# photodiode-opamp-tester-mk-2_0.net
KiCad netlist of a schematic drawn in EAGLE
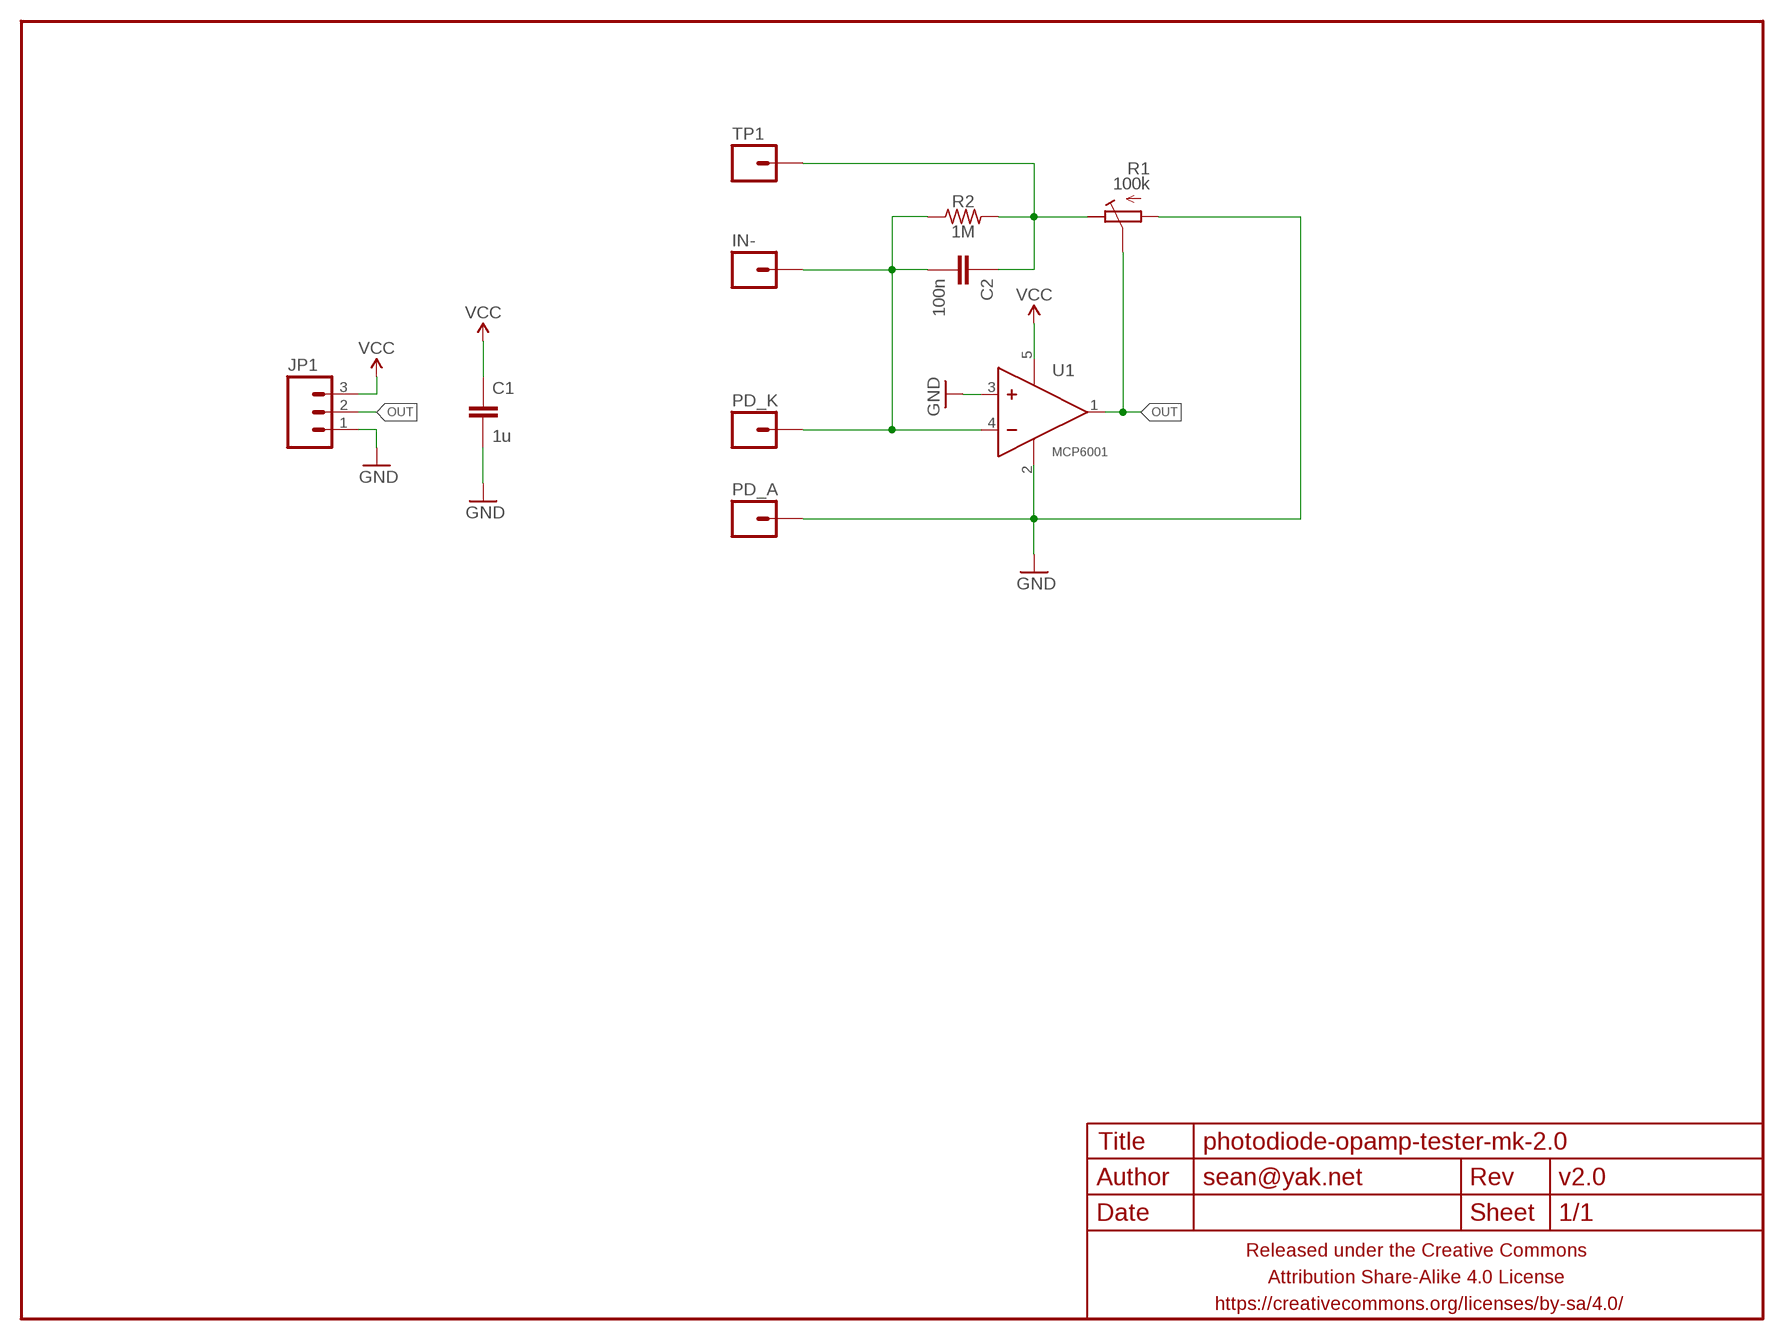
[diagram p0: schematic, sheet 1]

(export (version "E")
  (design (tool "Eeschema 10.0.6"))
  (components
    (comp (ref "C1")
      (value "1u")
      (footprint "eagle-import:C0603")
      (libsource (lib "eagle-import") (part "CAPACITOR-CERAMICC0603"))
    )
    (comp (ref "C2")
      (value "100n")
      (footprint "eagle-import:C0603")
      (libsource (lib "eagle-import") (part "CAPACITOR-CERAMICC0603"))
    )
    (comp (ref "FRAME1")
      (value "FRAME-LETTERNO_PACKAGE")
      (footprint "eagle-import:DUMMY")
      (fields (field (name "DESIGNER") "sean@yak.net") (field (name "VERSION") "v2.0"))
      (libsource (lib "eagle-import") (part "FRAME-LETTERNO_PACKAGE"))
    )
    (comp (ref "IN-")
      (value "M01OFFSET")
      (footprint "eagle-import:1X01_OFFSET")
      (libsource (lib "eagle-import") (part "M01OFFSET"))
    )
    (comp (ref "JP1")
      (value "M03PTH-CENTERED")
      (footprint "eagle-import:1X03-CENTERED")
      (libsource (lib "eagle-import") (part "M03PTH-CENTERED"))
    )
    (comp (ref "PD_A")
      (value "M01PTH-1.2MM-OCT")
      (footprint "eagle-import:1X01-1.2MM-OCT")
      (libsource (lib "eagle-import") (part "M01PTH-1.2MM-OCT"))
    )
    (comp (ref "PD_K")
      (value "M01PTH-1.2MM-OCT")
      (footprint "eagle-import:1X01-1.2MM-OCT")
      (libsource (lib "eagle-import") (part "M01PTH-1.2MM-OCT"))
    )
    (comp (ref "R1")
      (value "100k")
      (footprint "eagle-import:EVM3Y")
      (libsource (lib "eagle-import") (part "POTENTIOMETEREVM3Y"))
    )
    (comp (ref "R2")
      (value "1M")
      (footprint "eagle-import:R0603")
      (libsource (lib "eagle-import") (part "RESISTORR0603"))
    )
    (comp (ref "TP1")
      (value "M01OFFSET")
      (footprint "eagle-import:1X01_OFFSET")
      (libsource (lib "eagle-import") (part "M01OFFSET"))
    )
    (comp (ref "U1")
      (value "MCP6001")
      (footprint "eagle-import:SOT23-5")
      (libsource (lib "eagle-import") (part "MCP6001SOT23-5"))
    )
  )
  (nets
    (net (code "1") (name "GND") (class "Default")
      (node (ref "C1") (pin "2") (pinfunction "2_2") (pintype "passive"))
      (node (ref "JP1") (pin "1") (pinfunction "1_1") (pintype "passive"))
      (node (ref "PD_A") (pin "1") (pinfunction "1_1") (pintype "passive"))
      (node (ref "R1") (pin "A") (pinfunction "A_A") (pintype "passive"))
      (node (ref "U1") (pin "2") (pinfunction "V-_2") (pintype "power_in"))
      (node (ref "U1") (pin "3") (pinfunction "IN+_3") (pintype "input"))
    )
    (net (code "2") (name "Net-(C2-Pad1)") (class "Default")
      (node (ref "C2") (pin "1") (pinfunction "1_1") (pintype "passive"))
      (node (ref "R1") (pin "E") (pinfunction "E_E") (pintype "passive"))
      (node (ref "R2") (pin "2") (pinfunction "2_2") (pintype "passive"))
      (node (ref "TP1") (pin "1") (pinfunction "1_1") (pintype "passive"))
    )
    (net (code "3") (name "Net-(U1-IN-)") (class "Default")
      (node (ref "C2") (pin "2") (pinfunction "2_2") (pintype "passive"))
      (node (ref "IN-") (pin "1") (pinfunction "1_1") (pintype "passive"))
      (node (ref "PD_K") (pin "1") (pinfunction "1_1") (pintype "passive"))
      (node (ref "R2") (pin "1") (pinfunction "1_1") (pintype "passive"))
      (node (ref "U1") (pin "4") (pinfunction "IN-_4") (pintype "input"))
    )
    (net (code "4") (name "OUT") (class "Default")
      (node (ref "JP1") (pin "2") (pinfunction "2_2") (pintype "passive"))
      (node (ref "R1") (pin "S") (pinfunction "S_S") (pintype "passive"))
      (node (ref "U1") (pin "1") (pinfunction "OUT_1") (pintype "output"))
    )
    (net (code "5") (name "VCC") (class "Default")
      (node (ref "C1") (pin "1") (pinfunction "1_1") (pintype "passive"))
      (node (ref "JP1") (pin "3") (pinfunction "3_3") (pintype "passive"))
      (node (ref "U1") (pin "5") (pinfunction "V+_5") (pintype "power_in"))
    )
  )
)
